# 3_shkb_downstream_con.net
KiCad netlist of a schematic drawn in Altium Designer
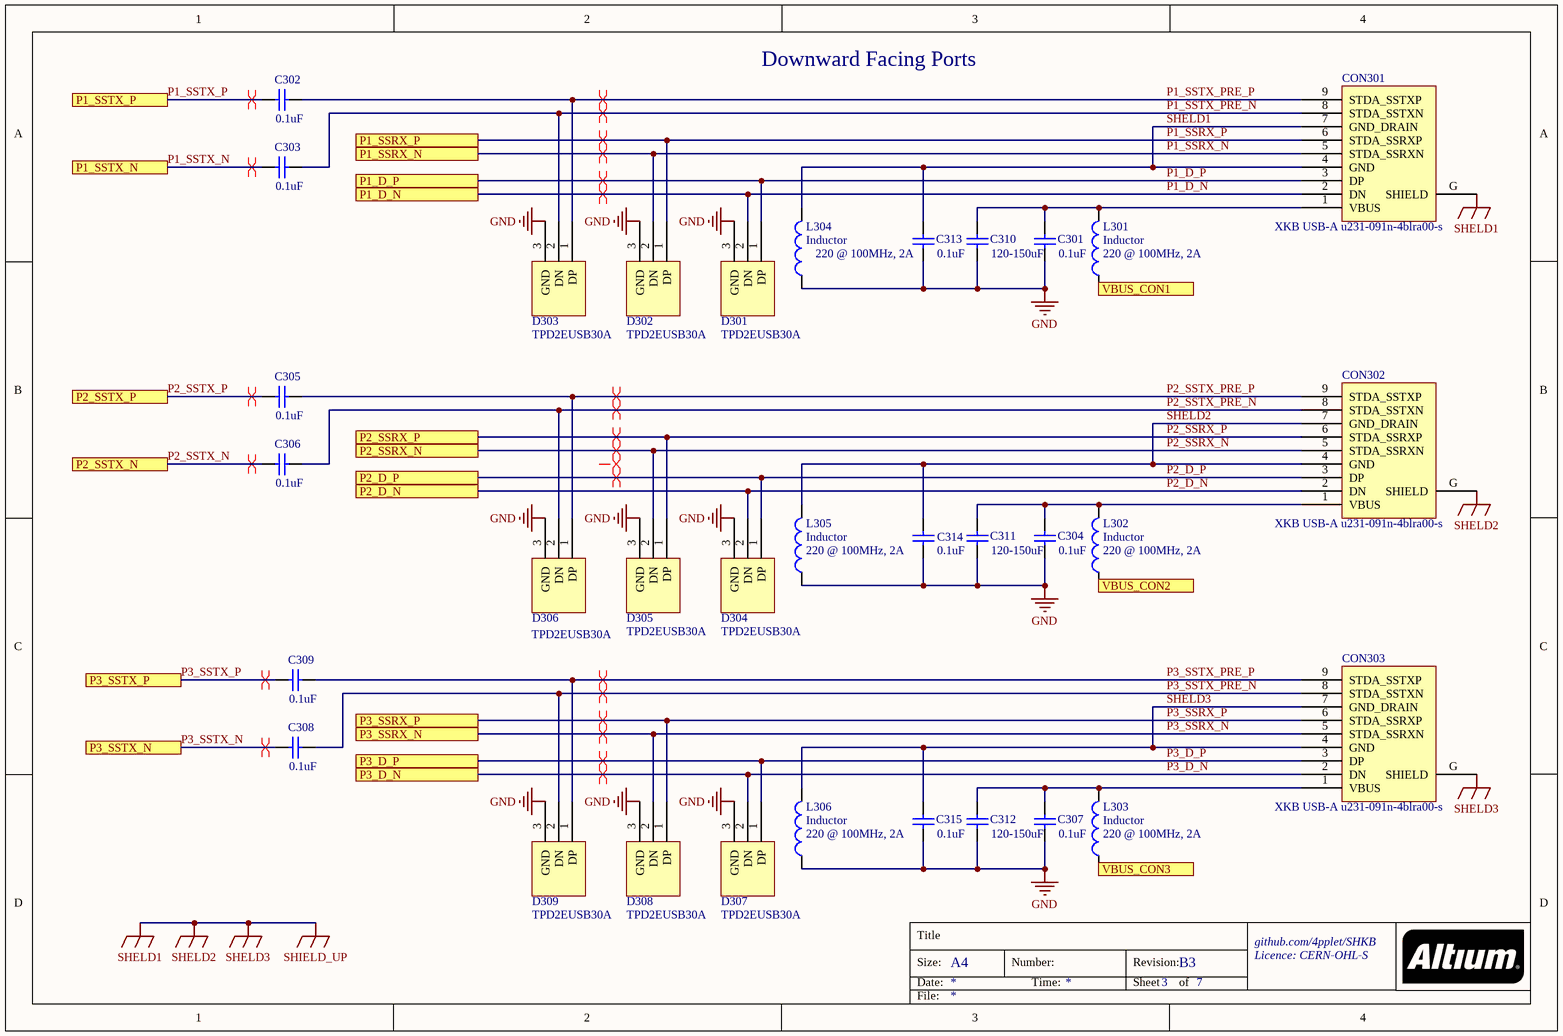
[diagram p0: 3_shkb_downstream_con.SchDoc]

(export (version "E")
  (design (tool "Eeschema 10.0.6"))
  (components
    (comp (ref "C301")
      (value "0.1uF")
      (footprint "C0603[1608]")
      (description "Capacitor")
      (fields (field (name "MFG") "KEMET") (field (name "LCSC PART #") "C14663"))
      (libsource (lib "Miscellaneous Devices") (part "Cap"))
    )
    (comp (ref "C302")
      (value "0.1uF")
      (footprint "C0402[1005]")
      (description "Capacitor")
      (fields (field (name "MFG") "KEMET") (field (name "LCSC PART #") "C1525"))
      (libsource (lib "Miscellaneous Devices") (part "Cap"))
    )
    (comp (ref "C303")
      (value "0.1uF")
      (footprint "C0402[1005]")
      (description "Capacitor")
      (fields (field (name "MFG") "KEMET") (field (name "LCSC PART #") "C1525"))
      (libsource (lib "Miscellaneous Devices") (part "Cap"))
    )
    (comp (ref "C304")
      (value "0.1uF")
      (footprint "C0603[1608]")
      (description "Capacitor")
      (fields (field (name "MFG") "KEMET") (field (name "LCSC PART #") "C14663"))
      (libsource (lib "Miscellaneous Devices") (part "Cap"))
    )
    (comp (ref "C305")
      (value "0.1uF")
      (footprint "C0402[1005]")
      (description "Capacitor")
      (fields (field (name "MFG") "KEMET") (field (name "LCSC PART #") "C1525"))
      (libsource (lib "Miscellaneous Devices") (part "Cap"))
    )
    (comp (ref "C306")
      (value "0.1uF")
      (footprint "C0402[1005]")
      (description "Capacitor")
      (fields (field (name "MFG") "KEMET") (field (name "LCSC PART #") "C1525"))
      (libsource (lib "Miscellaneous Devices") (part "Cap"))
    )
    (comp (ref "C307")
      (value "0.1uF")
      (footprint "C0603[1608]")
      (description "Capacitor")
      (fields (field (name "MFG") "KEMET") (field (name "LCSC PART #") "C14663"))
      (libsource (lib "Miscellaneous Devices") (part "Cap"))
    )
    (comp (ref "C308")
      (value "0.1uF")
      (footprint "C0402[1005]")
      (description "Capacitor")
      (fields (field (name "MFG") "KEMET") (field (name "LCSC PART #") "C1525"))
      (libsource (lib "Miscellaneous Devices") (part "Cap"))
    )
    (comp (ref "C309")
      (value "0.1uF")
      (footprint "C0402[1005]")
      (description "Capacitor")
      (fields (field (name "MFG") "KEMET") (field (name "LCSC PART #") "C1525"))
      (libsource (lib "Miscellaneous Devices") (part "Cap"))
    )
    (comp (ref "C310")
      (value "120-150uF")
      (footprint "C_9L_9M")
      (description "Capacitor")
      (fields (field (name "MFG") "Würth Elektronik") (field (name "MRF.PART") "OVZ121M1CTR-0807"))
      (libsource (lib "Miscellaneous Devices") (part "Cap"))
    )
    (comp (ref "C311")
      (value "120-150uF")
      (footprint "C_9L_9M")
      (description "Capacitor")
      (fields (field (name "MFG") "Würth Elektronik") (field (name "MRF.PART") "OVZ121M1CTR-0807"))
      (libsource (lib "Miscellaneous Devices") (part "Cap"))
    )
    (comp (ref "C312")
      (value "120-150uF")
      (footprint "C_9L_9M")
      (description "Capacitor")
      (fields (field (name "MFG") "Würth Elektronik") (field (name "MRF.PART") "OVZ121M1CTR-0807"))
      (libsource (lib "Miscellaneous Devices") (part "Cap"))
    )
    (comp (ref "C313")
      (value "0.1uF")
      (footprint "C0603[1608]")
      (description "Capacitor")
      (fields (field (name "MFG") "KEMET") (field (name "LCSC PART #") "C14663"))
      (libsource (lib "Miscellaneous Devices") (part "Cap"))
    )
    (comp (ref "C314")
      (value "0.1uF")
      (footprint "C0603[1608]")
      (description "Capacitor")
      (fields (field (name "MFG") "KEMET") (field (name "LCSC PART #") "C14663"))
      (libsource (lib "Miscellaneous Devices") (part "Cap"))
    )
    (comp (ref "C315")
      (value "0.1uF")
      (footprint "C0603[1608]")
      (description "Capacitor")
      (fields (field (name "MFG") "KEMET") (field (name "LCSC PART #") "C14663"))
      (libsource (lib "Miscellaneous Devices") (part "Cap"))
    )
    (comp (ref "CON301")
      (value "XKB USB-A u231-091n-4blra00-s")
      (footprint "XKB USB-A u231-091n-4blra00-s")
      (fields (field (name "LCSC PART #") "C381140") (field (name "MRF.PART") "U231-091N-4BLRA00-S-1"))
      (libsource (lib "lib") (part "XKB USB-A u231-091n-4blra00-s"))
    )
    (comp (ref "CON302")
      (value "XKB USB-A u231-091n-4blra00-s")
      (footprint "XKB USB-A u231-091n-4blra00-s")
      (fields (field (name "LCSC PART #") "C381140") (field (name "MRF.PART") "U231-091N-4BLRA00-S-1"))
      (libsource (lib "lib") (part "XKB USB-A u231-091n-4blra00-s"))
    )
    (comp (ref "CON303")
      (value "XKB USB-A u231-091n-4blra00-s")
      (footprint "XKB USB-A u231-091n-4blra00-s")
      (fields (field (name "LCSC PART #") "C381140") (field (name "MRF.PART") "U231-091N-4BLRA00-S-1"))
      (libsource (lib "lib") (part "XKB USB-A u231-091n-4blra00-s"))
    )
    (comp (ref "D301")
      (value "TPD2EUSB30A")
      (footprint "TPD2EUSB30A")
      (fields
        (field (name "MFG") "Texas Instruments")
        (field (name "LCSC PART #") "C94934")
        (field (name "MRF.PART") "TPD2EUSB30ADRTR")
      )
      (libsource (lib "lib") (part "TPD2EUSB30A"))
    )
    (comp (ref "D302")
      (value "TPD2EUSB30A")
      (footprint "TPD2EUSB30A")
      (fields
        (field (name "MFG") "Texas Instruments")
        (field (name "LCSC PART #") "C94934")
        (field (name "MRF.PART") "TPD2EUSB30ADRTR")
      )
      (libsource (lib "lib") (part "TPD2EUSB30A"))
    )
    (comp (ref "D303")
      (value "TPD2EUSB30A")
      (footprint "TPD2EUSB30A")
      (fields
        (field (name "MFG") "Texas Instruments")
        (field (name "LCSC PART #") "C94934")
        (field (name "MRF.PART") "TPD2EUSB30ADRTR")
      )
      (libsource (lib "lib") (part "TPD2EUSB30A"))
    )
    (comp (ref "D304")
      (value "TPD2EUSB30A")
      (footprint "TPD2EUSB30A")
      (fields
        (field (name "MFG") "Texas Instruments")
        (field (name "LCSC PART #") "C94934")
        (field (name "MRF.PART") "TPD2EUSB30ADRTR")
      )
      (libsource (lib "lib") (part "TPD2EUSB30A"))
    )
    (comp (ref "D305")
      (value "TPD2EUSB30A")
      (footprint "TPD2EUSB30A")
      (fields
        (field (name "MFG") "Texas Instruments")
        (field (name "LCSC PART #") "C94934")
        (field (name "MRF.PART") "TPD2EUSB30ADRTR")
      )
      (libsource (lib "lib") (part "TPD2EUSB30A"))
    )
    (comp (ref "D306")
      (value "TPD2EUSB30A")
      (footprint "TPD2EUSB30A")
      (fields
        (field (name "MFG") "Texas Instruments")
        (field (name "LCSC PART #") "C94934")
        (field (name "MRF.PART") "TPD2EUSB30ADRTR")
      )
      (libsource (lib "lib") (part "TPD2EUSB30A"))
    )
    (comp (ref "D307")
      (value "TPD2EUSB30A")
      (footprint "TPD2EUSB30A")
      (fields
        (field (name "MFG") "Texas Instruments")
        (field (name "LCSC PART #") "C94934")
        (field (name "MRF.PART") "TPD2EUSB30ADRTR")
      )
      (libsource (lib "lib") (part "TPD2EUSB30A"))
    )
    (comp (ref "D308")
      (value "TPD2EUSB30A")
      (footprint "TPD2EUSB30A")
      (fields
        (field (name "MFG") "Texas Instruments")
        (field (name "LCSC PART #") "C94934")
        (field (name "MRF.PART") "TPD2EUSB30ADRTR")
      )
      (libsource (lib "lib") (part "TPD2EUSB30A"))
    )
    (comp (ref "D309")
      (value "TPD2EUSB30A")
      (footprint "TPD2EUSB30A")
      (fields
        (field (name "MFG") "Texas Instruments")
        (field (name "LCSC PART #") "C94934")
        (field (name "MRF.PART") "TPD2EUSB30ADRTR")
      )
      (libsource (lib "lib") (part "TPD2EUSB30A"))
    )
    (comp (ref "L301")
      (value "Inductor")
      (footprint "L0603[1608]")
      (fields
        (field (name "ALTIUM_VALUE") "220 @ 100MHz, 2A")
        (field (name "MFG") "Murata Electronics North America")
        (field (name "LCSC PART #") "C85832")
        (field (name "MRF.PART") "BLM18KG331SN1D")
      )
      (libsource (lib "Miscellaneous Devices") (part "Inductor"))
    )
    (comp (ref "L302")
      (value "Inductor")
      (footprint "L0603[1608]")
      (fields
        (field (name "ALTIUM_VALUE") "220 @ 100MHz, 2A")
        (field (name "MFG") "Murata Electronics North America")
        (field (name "LCSC PART #") "C85832")
        (field (name "MRF.PART") "BLM18KG331SN1D")
      )
      (libsource (lib "Miscellaneous Devices") (part "Inductor"))
    )
    (comp (ref "L303")
      (value "Inductor")
      (footprint "L0603[1608]")
      (fields
        (field (name "ALTIUM_VALUE") "220 @ 100MHz, 2A")
        (field (name "MFG") "Murata Electronics North America")
        (field (name "LCSC PART #") "C85832")
        (field (name "MRF.PART") "BLM18KG331SN1D")
      )
      (libsource (lib "Miscellaneous Devices") (part "Inductor"))
    )
    (comp (ref "L304")
      (value "Inductor")
      (footprint "L0603[1608]")
      (fields
        (field (name "ALTIUM_VALUE") "220 @ 100MHz, 2A")
        (field (name "MFG") "Murata Electronics North America")
        (field (name "LCSC PART #") "C85832")
        (field (name "MRF.PART") "BLM18KG331SN1D")
      )
      (libsource (lib "Miscellaneous Devices") (part "Inductor"))
    )
    (comp (ref "L305")
      (value "Inductor")
      (footprint "L0603[1608]")
      (fields
        (field (name "ALTIUM_VALUE") "220 @ 100MHz, 2A")
        (field (name "MFG") "Murata Electronics North America")
        (field (name "LCSC PART #") "C85832")
        (field (name "MRF.PART") "BLM18KG331SN1D")
      )
      (libsource (lib "Miscellaneous Devices") (part "Inductor"))
    )
    (comp (ref "L306")
      (value "Inductor")
      (footprint "L0603[1608]")
      (fields
        (field (name "ALTIUM_VALUE") "220 @ 100MHz, 2A")
        (field (name "MFG") "Murata Electronics North America")
        (field (name "LCSC PART #") "C85832")
        (field (name "MRF.PART") "BLM18KG331SN1D")
      )
      (libsource (lib "Miscellaneous Devices") (part "Inductor"))
    )
  )
  (nets
    (net (code "1") (name "/P1_D_N") (class "Default")
      (node (ref "CON301") (pin "2") (pinfunction "DN_2") (pintype "passive"))
      (node (ref "D301") (pin "2") (pinfunction "DN_2") (pintype "passive"))
    )
    (net (code "2") (name "/P1_D_P") (class "Default")
      (node (ref "CON301") (pin "3") (pinfunction "DP_3") (pintype "passive"))
      (node (ref "D301") (pin "1") (pinfunction "DP_1") (pintype "passive"))
    )
    (net (code "3") (name "/P1_SSRX_N") (class "Default")
      (node (ref "CON301") (pin "5") (pinfunction "STDA_SSRXN_5") (pintype "passive"))
      (node (ref "D302") (pin "2") (pinfunction "DN_2") (pintype "passive"))
    )
    (net (code "4") (name "/P1_SSRX_P") (class "Default")
      (node (ref "CON301") (pin "6") (pinfunction "STDA_SSRXP_6") (pintype "passive"))
      (node (ref "D302") (pin "1") (pinfunction "DP_1") (pintype "passive"))
    )
    (net (code "5") (name "/P1_SSTX_N") (class "Default")
      (node (ref "C303") (pin "2") (pinfunction "2_2") (pintype "passive"))
    )
    (net (code "6") (name "/P1_SSTX_P") (class "Default")
      (node (ref "C302") (pin "2") (pinfunction "2_2") (pintype "passive"))
    )
    (net (code "7") (name "/P1_SSTX_PRE_N") (class "Default")
      (node (ref "C303") (pin "1") (pinfunction "1_1") (pintype "passive"))
      (node (ref "CON301") (pin "8") (pinfunction "STDA_SSTXN_8") (pintype "passive"))
      (node (ref "D303") (pin "2") (pinfunction "DN_2") (pintype "passive"))
    )
    (net (code "8") (name "/P1_SSTX_PRE_P") (class "Default")
      (node (ref "C302") (pin "1") (pinfunction "1_1") (pintype "passive"))
      (node (ref "CON301") (pin "9") (pinfunction "STDA_SSTXP_9") (pintype "passive"))
      (node (ref "D303") (pin "1") (pinfunction "DP_1") (pintype "passive"))
    )
    (net (code "9") (name "/P2_D_N") (class "Default")
      (node (ref "CON302") (pin "2") (pinfunction "DN_2") (pintype "passive"))
      (node (ref "D304") (pin "2") (pinfunction "DN_2") (pintype "passive"))
    )
    (net (code "10") (name "/P2_D_P") (class "Default")
      (node (ref "CON302") (pin "3") (pinfunction "DP_3") (pintype "passive"))
      (node (ref "D304") (pin "1") (pinfunction "DP_1") (pintype "passive"))
    )
    (net (code "11") (name "/P2_SSRX_N") (class "Default")
      (node (ref "CON302") (pin "5") (pinfunction "STDA_SSRXN_5") (pintype "passive"))
      (node (ref "D305") (pin "2") (pinfunction "DN_2") (pintype "passive"))
    )
    (net (code "12") (name "/P2_SSRX_P") (class "Default")
      (node (ref "CON302") (pin "6") (pinfunction "STDA_SSRXP_6") (pintype "passive"))
      (node (ref "D305") (pin "1") (pinfunction "DP_1") (pintype "passive"))
    )
    (net (code "13") (name "/P2_SSTX_N") (class "Default")
      (node (ref "C306") (pin "1") (pinfunction "1_1") (pintype "passive"))
    )
    (net (code "14") (name "/P2_SSTX_P") (class "Default")
      (node (ref "C305") (pin "1") (pinfunction "1_1") (pintype "passive"))
    )
    (net (code "15") (name "/P2_SSTX_PRE_N") (class "Default")
      (node (ref "C306") (pin "2") (pinfunction "2_2") (pintype "passive"))
      (node (ref "CON302") (pin "8") (pinfunction "STDA_SSTXN_8") (pintype "passive"))
      (node (ref "D306") (pin "2") (pinfunction "DN_2") (pintype "passive"))
    )
    (net (code "16") (name "/P2_SSTX_PRE_P") (class "Default")
      (node (ref "C305") (pin "2") (pinfunction "2_2") (pintype "passive"))
      (node (ref "CON302") (pin "9") (pinfunction "STDA_SSTXP_9") (pintype "passive"))
      (node (ref "D306") (pin "1") (pinfunction "DP_1") (pintype "passive"))
    )
    (net (code "17") (name "/P3_D_N") (class "Default")
      (node (ref "CON303") (pin "2") (pinfunction "DN_2") (pintype "passive"))
      (node (ref "D307") (pin "2") (pinfunction "DN_2") (pintype "passive"))
    )
    (net (code "18") (name "/P3_D_P") (class "Default")
      (node (ref "CON303") (pin "3") (pinfunction "DP_3") (pintype "passive"))
      (node (ref "D307") (pin "1") (pinfunction "DP_1") (pintype "passive"))
    )
    (net (code "19") (name "/P3_SSRX_N") (class "Default")
      (node (ref "CON303") (pin "5") (pinfunction "STDA_SSRXN_5") (pintype "passive"))
      (node (ref "D308") (pin "2") (pinfunction "DN_2") (pintype "passive"))
    )
    (net (code "20") (name "/P3_SSRX_P") (class "Default")
      (node (ref "CON303") (pin "6") (pinfunction "STDA_SSRXP_6") (pintype "passive"))
      (node (ref "D308") (pin "1") (pinfunction "DP_1") (pintype "passive"))
    )
    (net (code "21") (name "/P3_SSTX_N") (class "Default")
      (node (ref "C308") (pin "1") (pinfunction "1_1") (pintype "passive"))
    )
    (net (code "22") (name "/P3_SSTX_P") (class "Default")
      (node (ref "C309") (pin "1") (pinfunction "1_1") (pintype "passive"))
    )
    (net (code "23") (name "/P3_SSTX_PRE_N") (class "Default")
      (node (ref "C308") (pin "2") (pinfunction "2_2") (pintype "passive"))
      (node (ref "CON303") (pin "8") (pinfunction "STDA_SSTXN_8") (pintype "passive"))
      (node (ref "D309") (pin "2") (pinfunction "DN_2") (pintype "passive"))
    )
    (net (code "24") (name "/P3_SSTX_PRE_P") (class "Default")
      (node (ref "C309") (pin "2") (pinfunction "2_2") (pintype "passive"))
      (node (ref "CON303") (pin "9") (pinfunction "STDA_SSTXP_9") (pintype "passive"))
      (node (ref "D309") (pin "1") (pinfunction "DP_1") (pintype "passive"))
    )
    (net (code "25") (name "/VBUS_CON1") (class "Default")
      (node (ref "L301") (pin "1") (pinfunction "1_1") (pintype "passive"))
    )
    (net (code "26") (name "/VBUS_CON2") (class "Default")
      (node (ref "L302") (pin "1") (pinfunction "1_1") (pintype "passive"))
    )
    (net (code "27") (name "/VBUS_CON3") (class "Default")
      (node (ref "L303") (pin "1") (pinfunction "1_1") (pintype "passive"))
    )
    (net (code "28") (name "GND") (class "Default")
      (node (ref "C301") (pin "1") (pinfunction "1_1") (pintype "passive"))
      (node (ref "C304") (pin "1") (pinfunction "1_1") (pintype "passive"))
      (node (ref "C307") (pin "1") (pinfunction "1_1") (pintype "passive"))
      (node (ref "C310") (pin "1") (pinfunction "1_1") (pintype "passive"))
      (node (ref "C311") (pin "1") (pinfunction "1_1") (pintype "passive"))
      (node (ref "C312") (pin "1") (pinfunction "1_1") (pintype "passive"))
      (node (ref "C313") (pin "1") (pinfunction "1_1") (pintype "passive"))
      (node (ref "C314") (pin "1") (pinfunction "1_1") (pintype "passive"))
      (node (ref "C315") (pin "1") (pinfunction "1_1") (pintype "passive"))
      (node (ref "D301") (pin "3") (pinfunction "GND_3") (pintype "passive"))
      (node (ref "D302") (pin "3") (pinfunction "GND_3") (pintype "passive"))
      (node (ref "D303") (pin "3") (pinfunction "GND_3") (pintype "passive"))
      (node (ref "D304") (pin "3") (pinfunction "GND_3") (pintype "passive"))
      (node (ref "D305") (pin "3") (pinfunction "GND_3") (pintype "passive"))
      (node (ref "D306") (pin "3") (pinfunction "GND_3") (pintype "passive"))
      (node (ref "D307") (pin "3") (pinfunction "GND_3") (pintype "passive"))
      (node (ref "D308") (pin "3") (pinfunction "GND_3") (pintype "passive"))
      (node (ref "D309") (pin "3") (pinfunction "GND_3") (pintype "passive"))
      (node (ref "L304") (pin "1") (pinfunction "1_1") (pintype "passive"))
      (node (ref "L305") (pin "1") (pinfunction "1_1") (pintype "passive"))
      (node (ref "L306") (pin "1") (pinfunction "1_1") (pintype "passive"))
    )
    (net (code "29") (name "Net-(CON301-VBUS)") (class "Default")
      (node (ref "C301") (pin "2") (pinfunction "2_2") (pintype "passive"))
      (node (ref "C310") (pin "2") (pinfunction "2_2") (pintype "passive"))
      (node (ref "CON301") (pin "1") (pinfunction "VBUS_1") (pintype "passive"))
      (node (ref "L301") (pin "2") (pinfunction "2_2") (pintype "passive"))
    )
    (net (code "30") (name "Net-(CON302-VBUS)") (class "Default")
      (node (ref "C304") (pin "2") (pinfunction "2_2") (pintype "passive"))
      (node (ref "C311") (pin "2") (pinfunction "2_2") (pintype "passive"))
      (node (ref "CON302") (pin "1") (pinfunction "VBUS_1") (pintype "passive"))
      (node (ref "L302") (pin "2") (pinfunction "2_2") (pintype "passive"))
    )
    (net (code "31") (name "Net-(CON303-VBUS)") (class "Default")
      (node (ref "C307") (pin "2") (pinfunction "2_2") (pintype "passive"))
      (node (ref "C312") (pin "2") (pinfunction "2_2") (pintype "passive"))
      (node (ref "CON303") (pin "1") (pinfunction "VBUS_1") (pintype "passive"))
      (node (ref "L303") (pin "2") (pinfunction "2_2") (pintype "passive"))
    )
    (net (code "32") (name "SHELD1") (class "Default")
      (node (ref "C313") (pin "2") (pinfunction "2_2") (pintype "passive"))
      (node (ref "C314") (pin "2") (pinfunction "2_2") (pintype "passive"))
      (node (ref "C315") (pin "2") (pinfunction "2_2") (pintype "passive"))
      (node (ref "CON301") (pin "4") (pinfunction "GND_4") (pintype "passive"))
      (node (ref "CON301") (pin "7") (pinfunction "GND_DRAIN_7") (pintype "passive"))
      (node (ref "CON301") (pin "G") (pinfunction "SHIELD_G") (pintype "passive"))
      (node (ref "CON302") (pin "4") (pinfunction "GND_4") (pintype "passive"))
      (node (ref "CON302") (pin "7") (pinfunction "GND_DRAIN_7") (pintype "passive"))
      (node (ref "CON302") (pin "G") (pinfunction "SHIELD_G") (pintype "passive"))
      (node (ref "CON303") (pin "4") (pinfunction "GND_4") (pintype "passive"))
      (node (ref "CON303") (pin "7") (pinfunction "GND_DRAIN_7") (pintype "passive"))
      (node (ref "CON303") (pin "G") (pinfunction "SHIELD_G") (pintype "passive"))
      (node (ref "L304") (pin "2") (pinfunction "2_2") (pintype "passive"))
      (node (ref "L305") (pin "2") (pinfunction "2_2") (pintype "passive"))
      (node (ref "L306") (pin "2") (pinfunction "2_2") (pintype "passive"))
    )
  )
)
